# 19_SOLENOID_OF.net
KiCad netlist of a schematic drawn in Altium Designer
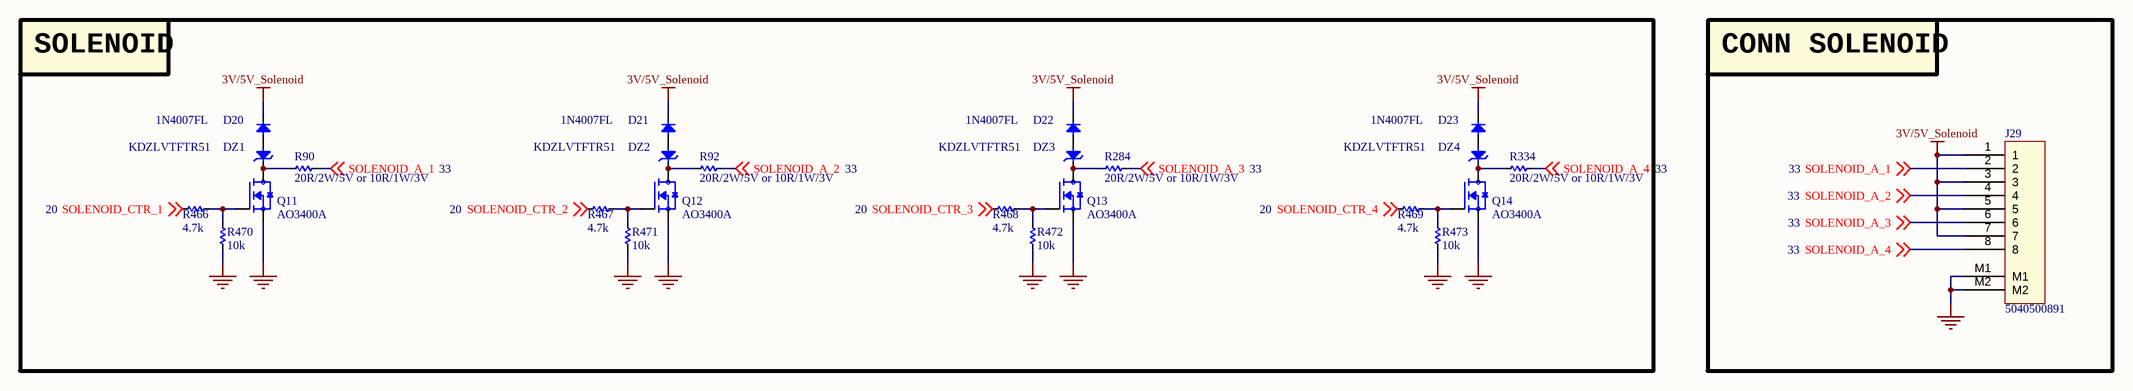
[diagram p0: 19_SOLENOID_OF.SchDoc]

(export (version "E")
  (design (tool "Eeschema 10.0.6"))
  (components
    (comp (ref "D20")
      (value "1N4007FL")
      (footprint "SOD3717X145N")
      (description "Default Diode")
      (fields (field (name "PUBLISHER") "Altium Limited"))
      (libsource (lib "LABLIB") (part "Diode SMD"))
    )
    (comp (ref "D21")
      (value "1N4007FL")
      (footprint "SOD3717X145N")
      (description "Default Diode")
      (fields (field (name "PUBLISHER") "Altium Limited"))
      (libsource (lib "LABLIB") (part "Diode SMD"))
    )
    (comp (ref "D22")
      (value "1N4007FL")
      (footprint "SOD3717X145N")
      (description "Default Diode")
      (fields (field (name "PUBLISHER") "Altium Limited"))
      (libsource (lib "LABLIB") (part "Diode SMD"))
    )
    (comp (ref "D23")
      (value "1N4007FL")
      (footprint "SOD3717X145N")
      (description "Default Diode")
      (fields (field (name "PUBLISHER") "Altium Limited"))
      (libsource (lib "LABLIB") (part "Diode SMD"))
    )
    (comp (ref "DZ1")
      (value "KDZLVTFTR51")
      (footprint "SOD3717X145N")
      (description "Zenner")
      (libsource (lib "LABLIB") (part "DIODE Zener"))
    )
    (comp (ref "DZ2")
      (value "KDZLVTFTR51")
      (footprint "SOD3717X145N")
      (description "Zenner")
      (libsource (lib "LABLIB") (part "DIODE Zener"))
    )
    (comp (ref "DZ3")
      (value "KDZLVTFTR51")
      (footprint "SOD3717X145N")
      (description "Zenner")
      (libsource (lib "LABLIB") (part "DIODE Zener"))
    )
    (comp (ref "DZ4")
      (value "KDZLVTFTR51")
      (footprint "SOD3717X145N")
      (description "Zenner")
      (libsource (lib "LABLIB") (part "DIODE Zener"))
    )
    (comp (ref "J29")
      (value "5040500891")
      (footprint "MOLEX_5040500891")
      (libsource (lib "LABLIB") (part "Header 8x1_2M"))
    )
    (comp (ref "Q11")
      (value "AO3400A")
      (footprint "SOT95P240X120-3N")
      (description "N-Channel 30 V 5.7A (Ta) 1.4W (Ta) Surface Mount SOT-23-3")
      (fields (field (name "MF") "Alpha & Omega Semiconductor"))
      (libsource (lib "LABLIB") (part "MOSFET_N"))
    )
    (comp (ref "Q12")
      (value "AO3400A")
      (footprint "SOT95P240X120-3N")
      (description "N-Channel 30 V 5.7A (Ta) 1.4W (Ta) Surface Mount SOT-23-3")
      (fields (field (name "MF") "Alpha & Omega Semiconductor"))
      (libsource (lib "LABLIB") (part "MOSFET_N"))
    )
    (comp (ref "Q13")
      (value "AO3400A")
      (footprint "SOT95P240X120-3N")
      (description "N-Channel 30 V 5.7A (Ta) 1.4W (Ta) Surface Mount SOT-23-3")
      (fields (field (name "MF") "Alpha & Omega Semiconductor"))
      (libsource (lib "LABLIB") (part "MOSFET_N"))
    )
    (comp (ref "Q14")
      (value "AO3400A")
      (footprint "SOT95P240X120-3N")
      (description "N-Channel 30 V 5.7A (Ta) 1.4W (Ta) Surface Mount SOT-23-3")
      (fields (field (name "MF") "Alpha & Omega Semiconductor"))
      (libsource (lib "LABLIB") (part "MOSFET_N"))
    )
    (comp (ref "R90")
      (value "20R/2W/5V or 10R/1W/3V")
      (footprint "RES_C_6331X65_N")
      (description "RES")
      (libsource (lib "LABLIB") (part "_RES_B_2"))
    )
    (comp (ref "R92")
      (value "20R/2W/5V or 10R/1W/3V")
      (footprint "RES_C_6331X65_N")
      (description "RES")
      (libsource (lib "LABLIB") (part "_RES_B_2"))
    )
    (comp (ref "R284")
      (value "20R/2W/5V or 10R/1W/3V")
      (footprint "RES_C_6331X65_N")
      (description "RES")
      (libsource (lib "LABLIB") (part "_RES_B_2"))
    )
    (comp (ref "R334")
      (value "20R/2W/5V or 10R/1W/3V")
      (footprint "RES_C_6331X65_N")
      (description "RES")
      (libsource (lib "LABLIB") (part "_RES_B_2"))
    )
    (comp (ref "R466")
      (value "4.7k")
      (footprint "RES_C_1005X40")
      (description "RES")
      (libsource (lib "LABLIB") (part "_RES_B_2"))
    )
    (comp (ref "R467")
      (value "4.7k")
      (footprint "RES_C_1005X40")
      (description "RES")
      (libsource (lib "LABLIB") (part "_RES_B_2"))
    )
    (comp (ref "R468")
      (value "4.7k")
      (footprint "RES_C_1005X40")
      (description "RES")
      (libsource (lib "LABLIB") (part "_RES_B_2"))
    )
    (comp (ref "R469")
      (value "4.7k")
      (footprint "RES_C_1005X40")
      (description "RES")
      (libsource (lib "LABLIB") (part "_RES_B_2"))
    )
    (comp (ref "R470")
      (value "10k")
      (footprint "RES_C_1005X40")
      (description "RES")
      (libsource (lib "LABLIB") (part "_RES_B_2"))
    )
    (comp (ref "R471")
      (value "10k")
      (footprint "RES_C_1005X40")
      (description "RES")
      (libsource (lib "LABLIB") (part "_RES_B_2"))
    )
    (comp (ref "R472")
      (value "10k")
      (footprint "RES_C_1005X40")
      (description "RES")
      (libsource (lib "LABLIB") (part "_RES_B_2"))
    )
    (comp (ref "R473")
      (value "10k")
      (footprint "RES_C_1005X40")
      (description "RES")
      (libsource (lib "LABLIB") (part "_RES_B_2"))
    )
  )
  (nets
    (net (code "1") (name "3V{slash}5V_Solenoid") (class "Default")
      (node (ref "D20") (pin "1") (pinfunction "K_1") (pintype "passive"))
      (node (ref "D21") (pin "1") (pinfunction "K_1") (pintype "passive"))
      (node (ref "D22") (pin "1") (pinfunction "K_1") (pintype "passive"))
      (node (ref "D23") (pin "1") (pinfunction "K_1") (pintype "passive"))
      (node (ref "J29") (pin "1") (pinfunction "1_1") (pintype "passive"))
      (node (ref "J29") (pin "3") (pinfunction "3_3") (pintype "passive"))
      (node (ref "J29") (pin "5") (pinfunction "5_5") (pintype "passive"))
      (node (ref "J29") (pin "7") (pinfunction "7_7") (pintype "passive"))
    )
    (net (code "2") (name "GND") (class "Default")
      (node (ref "J29") (pin "M1") (pinfunction "M1_M1") (pintype "passive"))
      (node (ref "J29") (pin "M2") (pinfunction "M2_M2") (pintype "passive"))
      (node (ref "Q11") (pin "2") (pinfunction "S_2") (pintype "passive"))
      (node (ref "Q12") (pin "2") (pinfunction "S_2") (pintype "passive"))
      (node (ref "Q13") (pin "2") (pinfunction "S_2") (pintype "passive"))
      (node (ref "Q14") (pin "2") (pinfunction "S_2") (pintype "passive"))
      (node (ref "R470") (pin "1") (pinfunction "1_1") (pintype "passive"))
      (node (ref "R471") (pin "1") (pinfunction "1_1") (pintype "passive"))
      (node (ref "R472") (pin "1") (pinfunction "1_1") (pintype "passive"))
      (node (ref "R473") (pin "1") (pinfunction "1_1") (pintype "passive"))
    )
    (net (code "3") (name "Net-(D20-A)") (class "Default")
      (node (ref "D20") (pin "2") (pinfunction "A_2") (pintype "passive"))
      (node (ref "DZ1") (pin "2") (pinfunction "A_2") (pintype "passive"))
    )
    (net (code "4") (name "Net-(D21-A)") (class "Default")
      (node (ref "D21") (pin "2") (pinfunction "A_2") (pintype "passive"))
      (node (ref "DZ2") (pin "2") (pinfunction "A_2") (pintype "passive"))
    )
    (net (code "5") (name "Net-(D22-A)") (class "Default")
      (node (ref "D22") (pin "2") (pinfunction "A_2") (pintype "passive"))
      (node (ref "DZ3") (pin "2") (pinfunction "A_2") (pintype "passive"))
    )
    (net (code "6") (name "Net-(D23-A)") (class "Default")
      (node (ref "D23") (pin "2") (pinfunction "A_2") (pintype "passive"))
      (node (ref "DZ4") (pin "2") (pinfunction "A_2") (pintype "passive"))
    )
    (net (code "7") (name "Net-(DZ1-K)") (class "Default")
      (node (ref "DZ1") (pin "1") (pinfunction "K_1") (pintype "passive"))
      (node (ref "Q11") (pin "3") (pinfunction "D_3") (pintype "passive"))
      (node (ref "R90") (pin "2") (pinfunction "2_2") (pintype "passive"))
    )
    (net (code "8") (name "Net-(DZ2-K)") (class "Default")
      (node (ref "DZ2") (pin "1") (pinfunction "K_1") (pintype "passive"))
      (node (ref "Q12") (pin "3") (pinfunction "D_3") (pintype "passive"))
      (node (ref "R92") (pin "2") (pinfunction "2_2") (pintype "passive"))
    )
    (net (code "9") (name "Net-(DZ3-K)") (class "Default")
      (node (ref "DZ3") (pin "1") (pinfunction "K_1") (pintype "passive"))
      (node (ref "Q13") (pin "3") (pinfunction "D_3") (pintype "passive"))
      (node (ref "R284") (pin "2") (pinfunction "2_2") (pintype "passive"))
    )
    (net (code "10") (name "Net-(DZ4-K)") (class "Default")
      (node (ref "DZ4") (pin "1") (pinfunction "K_1") (pintype "passive"))
      (node (ref "Q14") (pin "3") (pinfunction "D_3") (pintype "passive"))
      (node (ref "R334") (pin "2") (pinfunction "2_2") (pintype "passive"))
    )
    (net (code "11") (name "Net-(Q11-G)") (class "Default")
      (node (ref "Q11") (pin "1") (pinfunction "G_1") (pintype "passive"))
      (node (ref "R466") (pin "1") (pinfunction "1_1") (pintype "passive"))
      (node (ref "R470") (pin "2") (pinfunction "2_2") (pintype "passive"))
    )
    (net (code "12") (name "Net-(Q12-G)") (class "Default")
      (node (ref "Q12") (pin "1") (pinfunction "G_1") (pintype "passive"))
      (node (ref "R467") (pin "1") (pinfunction "1_1") (pintype "passive"))
      (node (ref "R471") (pin "2") (pinfunction "2_2") (pintype "passive"))
    )
    (net (code "13") (name "Net-(Q13-G)") (class "Default")
      (node (ref "Q13") (pin "1") (pinfunction "G_1") (pintype "passive"))
      (node (ref "R468") (pin "1") (pinfunction "1_1") (pintype "passive"))
      (node (ref "R472") (pin "2") (pinfunction "2_2") (pintype "passive"))
    )
    (net (code "14") (name "Net-(Q14-G)") (class "Default")
      (node (ref "Q14") (pin "1") (pinfunction "G_1") (pintype "passive"))
      (node (ref "R469") (pin "1") (pinfunction "1_1") (pintype "passive"))
      (node (ref "R473") (pin "2") (pinfunction "2_2") (pintype "passive"))
    )
    (net (code "15") (name "SOLENOID_A_1") (class "Default")
      (node (ref "J29") (pin "2") (pinfunction "2_2") (pintype "passive"))
      (node (ref "R90") (pin "1") (pinfunction "1_1") (pintype "passive"))
    )
    (net (code "16") (name "SOLENOID_A_2") (class "Default")
      (node (ref "J29") (pin "4") (pinfunction "4_4") (pintype "passive"))
      (node (ref "R92") (pin "1") (pinfunction "1_1") (pintype "passive"))
    )
    (net (code "17") (name "SOLENOID_A_3") (class "Default")
      (node (ref "J29") (pin "6") (pinfunction "6_6") (pintype "passive"))
      (node (ref "R284") (pin "1") (pinfunction "1_1") (pintype "passive"))
    )
    (net (code "18") (name "SOLENOID_A_4") (class "Default")
      (node (ref "J29") (pin "8") (pinfunction "8_8") (pintype "passive"))
      (node (ref "R334") (pin "1") (pinfunction "1_1") (pintype "passive"))
    )
    (net (code "19") (name "SOLENOID_CTR_1") (class "Default")
      (node (ref "R466") (pin "2") (pinfunction "2_2") (pintype "passive"))
    )
    (net (code "20") (name "SOLENOID_CTR_2") (class "Default")
      (node (ref "R467") (pin "2") (pinfunction "2_2") (pintype "passive"))
    )
    (net (code "21") (name "SOLENOID_CTR_3") (class "Default")
      (node (ref "R468") (pin "2") (pinfunction "2_2") (pintype "passive"))
    )
    (net (code "22") (name "SOLENOID_CTR_4") (class "Default")
      (node (ref "R469") (pin "2") (pinfunction "2_2") (pintype "passive"))
    )
  )
)
